# arduino_Uno_Rev3-02-TH.net
KiCad netlist of a schematic drawn in EAGLE
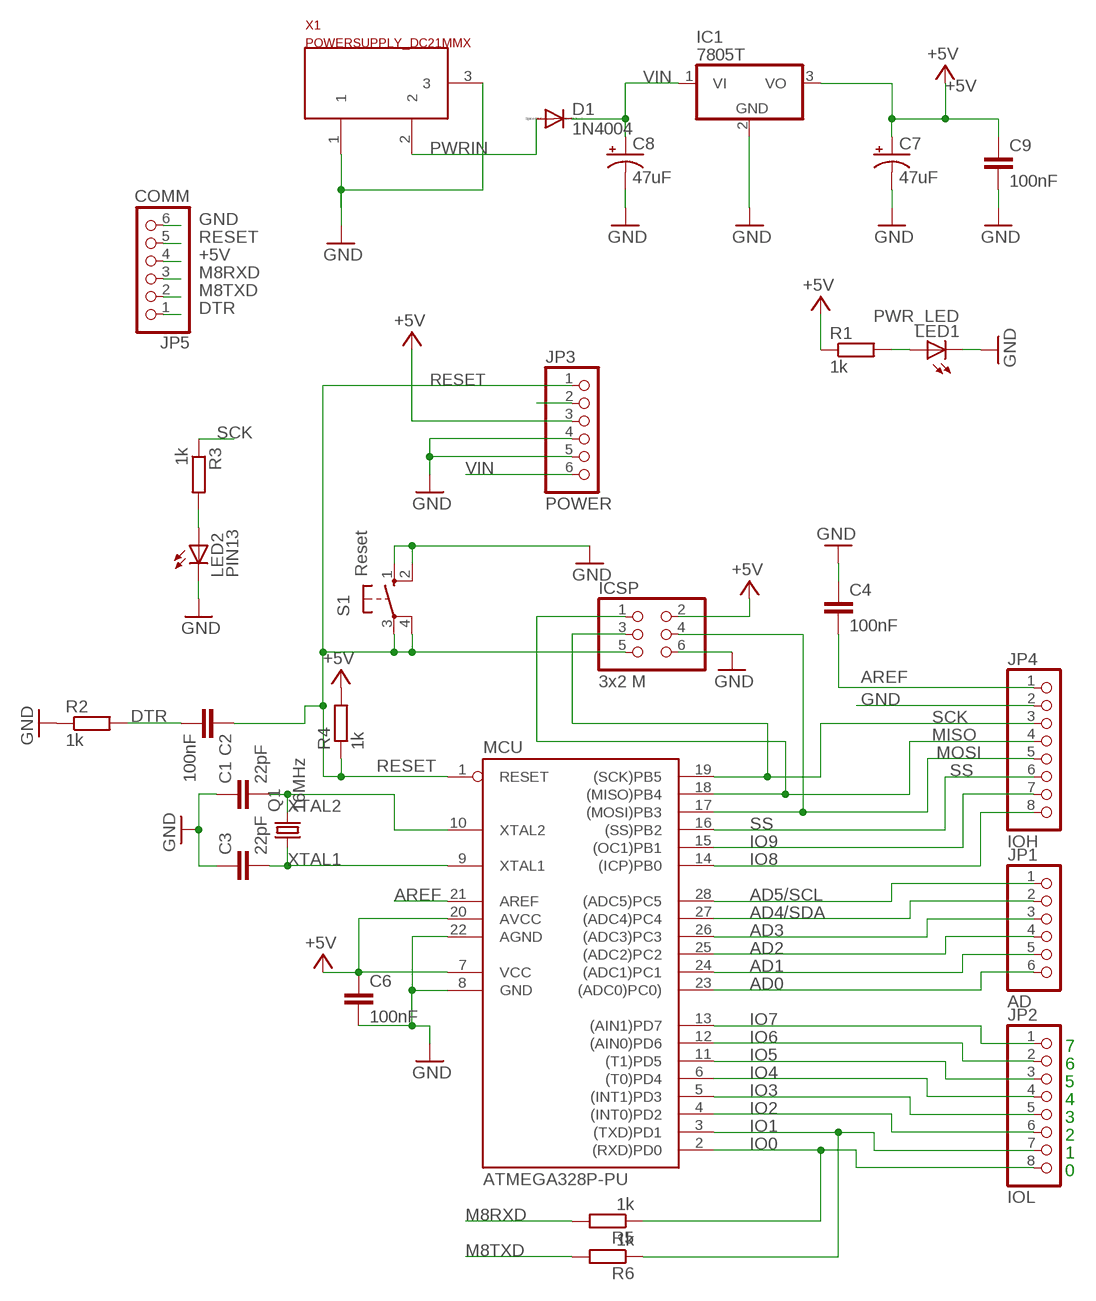
[diagram p0: schematic, sheet 1]

(export (version "E")
  (design (tool "Eeschema 10.0.6"))
  (components
    (comp (ref "C1")
      (value "22pF")
      (footprint "eagle-import:C2.5-2")
      (libsource (lib "eagle-import") (part "C2.5/2"))
    )
    (comp (ref "C2")
      (value "100nF")
      (footprint "eagle-import:C2.5-3")
      (libsource (lib "eagle-import") (part "C2,5-3"))
    )
    (comp (ref "C3")
      (value "22pF")
      (footprint "eagle-import:C2.5-2")
      (libsource (lib "eagle-import") (part "C2.5/2"))
    )
    (comp (ref "C4")
      (value "100nF")
      (footprint "eagle-import:C2.5-3")
      (libsource (lib "eagle-import") (part "C2,5-3"))
    )
    (comp (ref "C6")
      (value "100nF")
      (footprint "eagle-import:C2.5-3")
      (libsource (lib "eagle-import") (part "C2,5-3"))
    )
    (comp (ref "C7")
      (value "47uF")
      (footprint "eagle-import:E3,5-8")
      (libsource (lib "eagle-import") (part "CPOL-USE3.5-8"))
    )
    (comp (ref "C8")
      (value "47uF")
      (footprint "eagle-import:E3,5-8")
      (libsource (lib "eagle-import") (part "CPOL-USE3.5-8"))
    )
    (comp (ref "C9")
      (value "100nF")
      (footprint "eagle-import:C2.5-3")
      (libsource (lib "eagle-import") (part "C2,5-3"))
    )
    (comp (ref "D1")
      (value "1N4004")
      (footprint "eagle-import:DO41-10")
      (libsource (lib "eagle-import") (part "1N4004"))
    )
    (comp (ref "IC1")
      (value "7805T")
      (footprint "eagle-import:TO220H")
      (libsource (lib "eagle-import") (part "78T05"))
    )
    (comp (ref "ICSP")
      (value "3x2 M")
      (footprint "eagle-import:2X03")
      (libsource (lib "eagle-import") (part "PINHD-2X3"))
    )
    (comp (ref "JP1")
      (value "AD")
      (footprint "eagle-import:1X06")
      (libsource (lib "eagle-import") (part "PINHD-1X6"))
    )
    (comp (ref "JP2")
      (value "IOL")
      (footprint "eagle-import:1X08-BIG")
      (libsource (lib "eagle-import") (part "PINHD-1X8BIG"))
    )
    (comp (ref "JP3")
      (value "POWER")
      (footprint "eagle-import:1X06")
      (libsource (lib "eagle-import") (part "PINHD-1X6"))
    )
    (comp (ref "JP4")
      (value "IOH")
      (footprint "eagle-import:1X08-BIG")
      (libsource (lib "eagle-import") (part "PINHD-1X8BIG"))
    )
    (comp (ref "JP5")
      (value "COMM")
      (footprint "eagle-import:1X06")
      (libsource (lib "eagle-import") (part "PINHD-1X6"))
    )
    (comp (ref "LED1")
      (value "PWR_LED")
      (footprint "eagle-import:LED3MM")
      (libsource (lib "eagle-import") (part "LED3MM"))
    )
    (comp (ref "LED2")
      (value "PIN13")
      (footprint "eagle-import:LED5MM")
      (libsource (lib "eagle-import") (part "LED5MM"))
    )
    (comp (ref "MCU")
      (value "ATMEGA328P-PU")
      (footprint "eagle-import:DIL28-3")
      (libsource (lib "eagle-import") (part "ATMEGA328P-PU"))
    )
    (comp (ref "Q1")
      (value "16MHz")
      (footprint "eagle-import:HC49_S")
      (libsource (lib "eagle-import") (part "CRYSTALHC49S"))
    )
    (comp (ref "R1")
      (value "1k")
      (footprint "eagle-import:0207_10")
      (libsource (lib "eagle-import") (part "R-EU_0207/10"))
    )
    (comp (ref "R2")
      (value "1k")
      (footprint "eagle-import:0207_10")
      (libsource (lib "eagle-import") (part "R-EU_0207/10"))
    )
    (comp (ref "R3")
      (value "1k")
      (footprint "eagle-import:0207_10")
      (libsource (lib "eagle-import") (part "R-EU_0207/10"))
    )
    (comp (ref "R4")
      (value "1k")
      (footprint "eagle-import:0207_10")
      (libsource (lib "eagle-import") (part "R-EU_0207/10"))
    )
    (comp (ref "R5")
      (value "1k")
      (footprint "eagle-import:0207_10")
      (libsource (lib "eagle-import") (part "R-EU_0207/10"))
    )
    (comp (ref "R6")
      (value "1k")
      (footprint "eagle-import:0207_10")
      (libsource (lib "eagle-import") (part "R-EU_0207/10"))
    )
    (comp (ref "S1")
      (value "Reset")
      (footprint "eagle-import:B3F-10XX")
      (fields (field (name "MPN") "B3F-1000"))
      (libsource (lib "eagle-import") (part "10-XX"))
    )
    (comp (ref "X1")
      (value "POWERSUPPLY_DC21MMX")
      (footprint "eagle-import:POWERSUPPLY_DC-21MM")
      (libsource (lib "eagle-import") (part "POWERSUPPLY_DC21MMX"))
    )
  )
  (nets
    (net (code "1") (name "+5V") (class "Default")
      (node (ref "C6") (pin "1") (pinfunction "1_1") (pintype "passive"))
      (node (ref "C7") (pin "+") (pinfunction "+_+") (pintype "passive"))
      (node (ref "C9") (pin "1") (pinfunction "1_1") (pintype "passive"))
      (node (ref "IC1") (pin "3") (pinfunction "VO_3") (pintype "passive"))
      (node (ref "ICSP") (pin "2") (pinfunction "2_2") (pintype "passive"))
      (node (ref "JP3") (pin "3") (pinfunction "3_3") (pintype "passive"))
      (node (ref "JP5") (pin "4") (pinfunction "4_4") (pintype "passive"))
      (node (ref "MCU") (pin "20") (pinfunction "AVCC_20") (pintype "power_in"))
      (node (ref "MCU") (pin "7") (pinfunction "VCC_7") (pintype "power_in"))
      (node (ref "R1") (pin "1") (pinfunction "1_1") (pintype "passive"))
      (node (ref "R4") (pin "2") (pinfunction "2_2") (pintype "passive"))
    )
    (net (code "2") (name "/AD0") (class "Default")
      (node (ref "JP1") (pin "6") (pinfunction "6_6") (pintype "passive"))
      (node (ref "MCU") (pin "23") (pinfunction "(ADC0)PC0)_23") (pintype "bidirectional"))
    )
    (net (code "3") (name "/AD1") (class "Default")
      (node (ref "JP1") (pin "5") (pinfunction "5_5") (pintype "passive"))
      (node (ref "MCU") (pin "24") (pinfunction "(ADC1)PC1_24") (pintype "bidirectional"))
    )
    (net (code "4") (name "/AD2") (class "Default")
      (node (ref "JP1") (pin "4") (pinfunction "4_4") (pintype "passive"))
      (node (ref "MCU") (pin "25") (pinfunction "(ADC2)PC2_25") (pintype "bidirectional"))
    )
    (net (code "5") (name "/AD3") (class "Default")
      (node (ref "JP1") (pin "3") (pinfunction "3_3") (pintype "passive"))
      (node (ref "MCU") (pin "26") (pinfunction "(ADC3)PC3_26") (pintype "bidirectional"))
    )
    (net (code "6") (name "/AD4{slash}SDA") (class "Default")
      (node (ref "JP1") (pin "2") (pinfunction "2_2") (pintype "passive"))
      (node (ref "MCU") (pin "27") (pinfunction "(ADC4)PC4_27") (pintype "bidirectional"))
    )
    (net (code "7") (name "/AD5{slash}SCL") (class "Default")
      (node (ref "JP1") (pin "1") (pinfunction "1_1") (pintype "passive"))
      (node (ref "MCU") (pin "28") (pinfunction "(ADC5)PC5_28") (pintype "bidirectional"))
    )
    (net (code "8") (name "/AREF") (class "Default")
      (node (ref "C4") (pin "2") (pinfunction "2_2") (pintype "passive"))
      (node (ref "JP4") (pin "1") (pinfunction "1_1") (pintype "passive"))
      (node (ref "MCU") (pin "21") (pinfunction "AREF_21") (pintype "passive"))
    )
    (net (code "9") (name "/DTR") (class "Default")
      (node (ref "C2") (pin "2") (pinfunction "2_2") (pintype "passive"))
      (node (ref "JP5") (pin "1") (pinfunction "1_1") (pintype "passive"))
      (node (ref "R2") (pin "2") (pinfunction "2_2") (pintype "passive"))
    )
    (net (code "10") (name "/IO0") (class "Default")
      (node (ref "JP2") (pin "8") (pinfunction "8_8") (pintype "passive"))
      (node (ref "MCU") (pin "2") (pinfunction "(RXD)PD0_2") (pintype "bidirectional"))
      (node (ref "R5") (pin "1") (pinfunction "1_1") (pintype "passive"))
    )
    (net (code "11") (name "/IO1") (class "Default")
      (node (ref "JP2") (pin "7") (pinfunction "7_7") (pintype "passive"))
      (node (ref "MCU") (pin "3") (pinfunction "(TXD)PD1_3") (pintype "bidirectional"))
      (node (ref "R6") (pin "1") (pinfunction "1_1") (pintype "passive"))
    )
    (net (code "12") (name "/IO2") (class "Default")
      (node (ref "JP2") (pin "6") (pinfunction "6_6") (pintype "passive"))
      (node (ref "MCU") (pin "4") (pinfunction "(INT0)PD2_4") (pintype "bidirectional"))
    )
    (net (code "13") (name "/IO3") (class "Default")
      (node (ref "JP2") (pin "5") (pinfunction "5_5") (pintype "passive"))
      (node (ref "MCU") (pin "5") (pinfunction "(INT1)PD3_5") (pintype "bidirectional"))
    )
    (net (code "14") (name "/IO4") (class "Default")
      (node (ref "JP2") (pin "4") (pinfunction "4_4") (pintype "passive"))
      (node (ref "MCU") (pin "6") (pinfunction "(T0)PD4_6") (pintype "bidirectional"))
    )
    (net (code "15") (name "/IO5") (class "Default")
      (node (ref "JP2") (pin "3") (pinfunction "3_3") (pintype "passive"))
      (node (ref "MCU") (pin "11") (pinfunction "(T1)PD5_11") (pintype "bidirectional"))
    )
    (net (code "16") (name "/IO6") (class "Default")
      (node (ref "JP2") (pin "2") (pinfunction "2_2") (pintype "passive"))
      (node (ref "MCU") (pin "12") (pinfunction "(AIN0)PD6_12") (pintype "bidirectional"))
    )
    (net (code "17") (name "/IO7") (class "Default")
      (node (ref "JP2") (pin "1") (pinfunction "1_1") (pintype "passive"))
      (node (ref "MCU") (pin "13") (pinfunction "(AIN1)PD7_13") (pintype "bidirectional"))
    )
    (net (code "18") (name "/IO8") (class "Default")
      (node (ref "JP4") (pin "8") (pinfunction "8_8") (pintype "passive"))
      (node (ref "MCU") (pin "14") (pinfunction "(ICP)PB0_14") (pintype "bidirectional"))
    )
    (net (code "19") (name "/IO9") (class "Default")
      (node (ref "JP4") (pin "7") (pinfunction "7_7") (pintype "passive"))
      (node (ref "MCU") (pin "15") (pinfunction "(OC1)PB1_15") (pintype "bidirectional"))
    )
    (net (code "20") (name "/M8RXD") (class "Default")
      (node (ref "JP5") (pin "3") (pinfunction "3_3") (pintype "passive"))
      (node (ref "R5") (pin "2") (pinfunction "2_2") (pintype "passive"))
    )
    (net (code "21") (name "/M8TXD") (class "Default")
      (node (ref "JP5") (pin "2") (pinfunction "2_2") (pintype "passive"))
      (node (ref "R6") (pin "2") (pinfunction "2_2") (pintype "passive"))
    )
    (net (code "22") (name "/MISO") (class "Default")
      (node (ref "ICSP") (pin "1") (pinfunction "1_1") (pintype "passive"))
      (node (ref "JP4") (pin "4") (pinfunction "4_4") (pintype "passive"))
      (node (ref "MCU") (pin "18") (pinfunction "(MISO)PB4_18") (pintype "bidirectional"))
    )
    (net (code "23") (name "/MOSI") (class "Default")
      (node (ref "ICSP") (pin "4") (pinfunction "4_4") (pintype "passive"))
      (node (ref "JP4") (pin "5") (pinfunction "5_5") (pintype "passive"))
      (node (ref "MCU") (pin "17") (pinfunction "(MOSI)PB3_17") (pintype "bidirectional"))
    )
    (net (code "24") (name "/PWRIN") (class "Default")
      (node (ref "D1") (pin "A") (pinfunction "A_A") (pintype "passive"))
      (node (ref "X1") (pin "2") (pinfunction "2_2") (pintype "power_in"))
    )
    (net (code "25") (name "/RESET") (class "Default")
      (node (ref "C2") (pin "1") (pinfunction "1_1") (pintype "passive"))
      (node (ref "ICSP") (pin "5") (pinfunction "5_5") (pintype "passive"))
      (node (ref "JP3") (pin "1") (pinfunction "1_1") (pintype "passive"))
      (node (ref "JP5") (pin "5") (pinfunction "5_5") (pintype "passive"))
      (node (ref "MCU") (pin "1") (pinfunction "RESET_1") (pintype "input"))
      (node (ref "R4") (pin "1") (pinfunction "1_1") (pintype "passive"))
      (node (ref "S1") (pin "3") (pinfunction "P_3") (pintype "passive"))
      (node (ref "S1") (pin "4") (pinfunction "P1_4") (pintype "passive"))
    )
    (net (code "26") (name "/SCK") (class "Default")
      (node (ref "ICSP") (pin "3") (pinfunction "3_3") (pintype "passive"))
      (node (ref "JP4") (pin "3") (pinfunction "3_3") (pintype "passive"))
      (node (ref "MCU") (pin "19") (pinfunction "(SCK)PB5_19") (pintype "bidirectional"))
      (node (ref "R3") (pin "1") (pinfunction "1_1") (pintype "passive"))
    )
    (net (code "27") (name "/SS") (class "Default")
      (node (ref "JP4") (pin "6") (pinfunction "6_6") (pintype "passive"))
      (node (ref "MCU") (pin "16") (pinfunction "(SS)PB2_16") (pintype "bidirectional"))
    )
    (net (code "28") (name "/VIN") (class "Default")
      (node (ref "C8") (pin "+") (pinfunction "+_+") (pintype "passive"))
      (node (ref "D1") (pin "C") (pinfunction "C_C") (pintype "passive"))
      (node (ref "IC1") (pin "1") (pinfunction "VI_1") (pintype "input"))
      (node (ref "JP3") (pin "6") (pinfunction "6_6") (pintype "passive"))
    )
    (net (code "29") (name "/XTAL1") (class "Default")
      (node (ref "C3") (pin "2") (pinfunction "2_2") (pintype "passive"))
      (node (ref "MCU") (pin "9") (pinfunction "XTAL1_9") (pintype "bidirectional"))
      (node (ref "Q1") (pin "1") (pinfunction "1_1") (pintype "passive"))
    )
    (net (code "30") (name "/XTAL2") (class "Default")
      (node (ref "C1") (pin "2") (pinfunction "2_2") (pintype "passive"))
      (node (ref "MCU") (pin "10") (pinfunction "XTAL2_10") (pintype "bidirectional"))
      (node (ref "Q1") (pin "2") (pinfunction "2_2") (pintype "passive"))
    )
    (net (code "31") (name "GND") (class "Default")
      (node (ref "C1") (pin "1") (pinfunction "1_1") (pintype "passive"))
      (node (ref "C3") (pin "1") (pinfunction "1_1") (pintype "passive"))
      (node (ref "C4") (pin "1") (pinfunction "1_1") (pintype "passive"))
      (node (ref "C6") (pin "2") (pinfunction "2_2") (pintype "passive"))
      (node (ref "C7") (pin "-") (pinfunction "-_-") (pintype "passive"))
      (node (ref "C8") (pin "-") (pinfunction "-_-") (pintype "passive"))
      (node (ref "C9") (pin "2") (pinfunction "2_2") (pintype "passive"))
      (node (ref "IC1") (pin "2") (pinfunction "GND_2") (pintype "passive"))
      (node (ref "ICSP") (pin "6") (pinfunction "6_6") (pintype "passive"))
      (node (ref "JP3") (pin "4") (pinfunction "4_4") (pintype "passive"))
      (node (ref "JP3") (pin "5") (pinfunction "5_5") (pintype "passive"))
      (node (ref "JP4") (pin "2") (pinfunction "2_2") (pintype "passive"))
      (node (ref "JP5") (pin "6") (pinfunction "6_6") (pintype "passive"))
      (node (ref "LED1") (pin "K") (pinfunction "C_K") (pintype "passive"))
      (node (ref "LED2") (pin "K") (pinfunction "C_K") (pintype "passive"))
      (node (ref "MCU") (pin "22") (pinfunction "AGND_22") (pintype "power_in"))
      (node (ref "MCU") (pin "8") (pinfunction "GND_8") (pintype "power_in"))
      (node (ref "R2") (pin "1") (pinfunction "1_1") (pintype "passive"))
      (node (ref "S1") (pin "1") (pinfunction "S_1") (pintype "passive"))
      (node (ref "S1") (pin "2") (pinfunction "S1_2") (pintype "passive"))
      (node (ref "X1") (pin "1") (pinfunction "1_1") (pintype "power_in"))
      (node (ref "X1") (pin "3") (pinfunction "3_3") (pintype "power_in"))
    )
    (net (code "32") (name "Net-(LED1-PadA)") (class "Default")
      (node (ref "LED1") (pin "A") (pinfunction "A_A") (pintype "passive"))
      (node (ref "R1") (pin "2") (pinfunction "2_2") (pintype "passive"))
    )
    (net (code "33") (name "Net-(LED2-PadA)") (class "Default")
      (node (ref "LED2") (pin "A") (pinfunction "A_A") (pintype "passive"))
      (node (ref "R3") (pin "2") (pinfunction "2_2") (pintype "passive"))
    )
    (net (code "34") (name "unconnected-(JP3-Pad2)") (class "Default")
      (node (ref "JP3") (pin "2") (pinfunction "2_2") (pintype "passive"))
    )
  )
)
